# EPS_Connectors_PC-104.net
KiCad netlist of a schematic drawn in Altium Designer
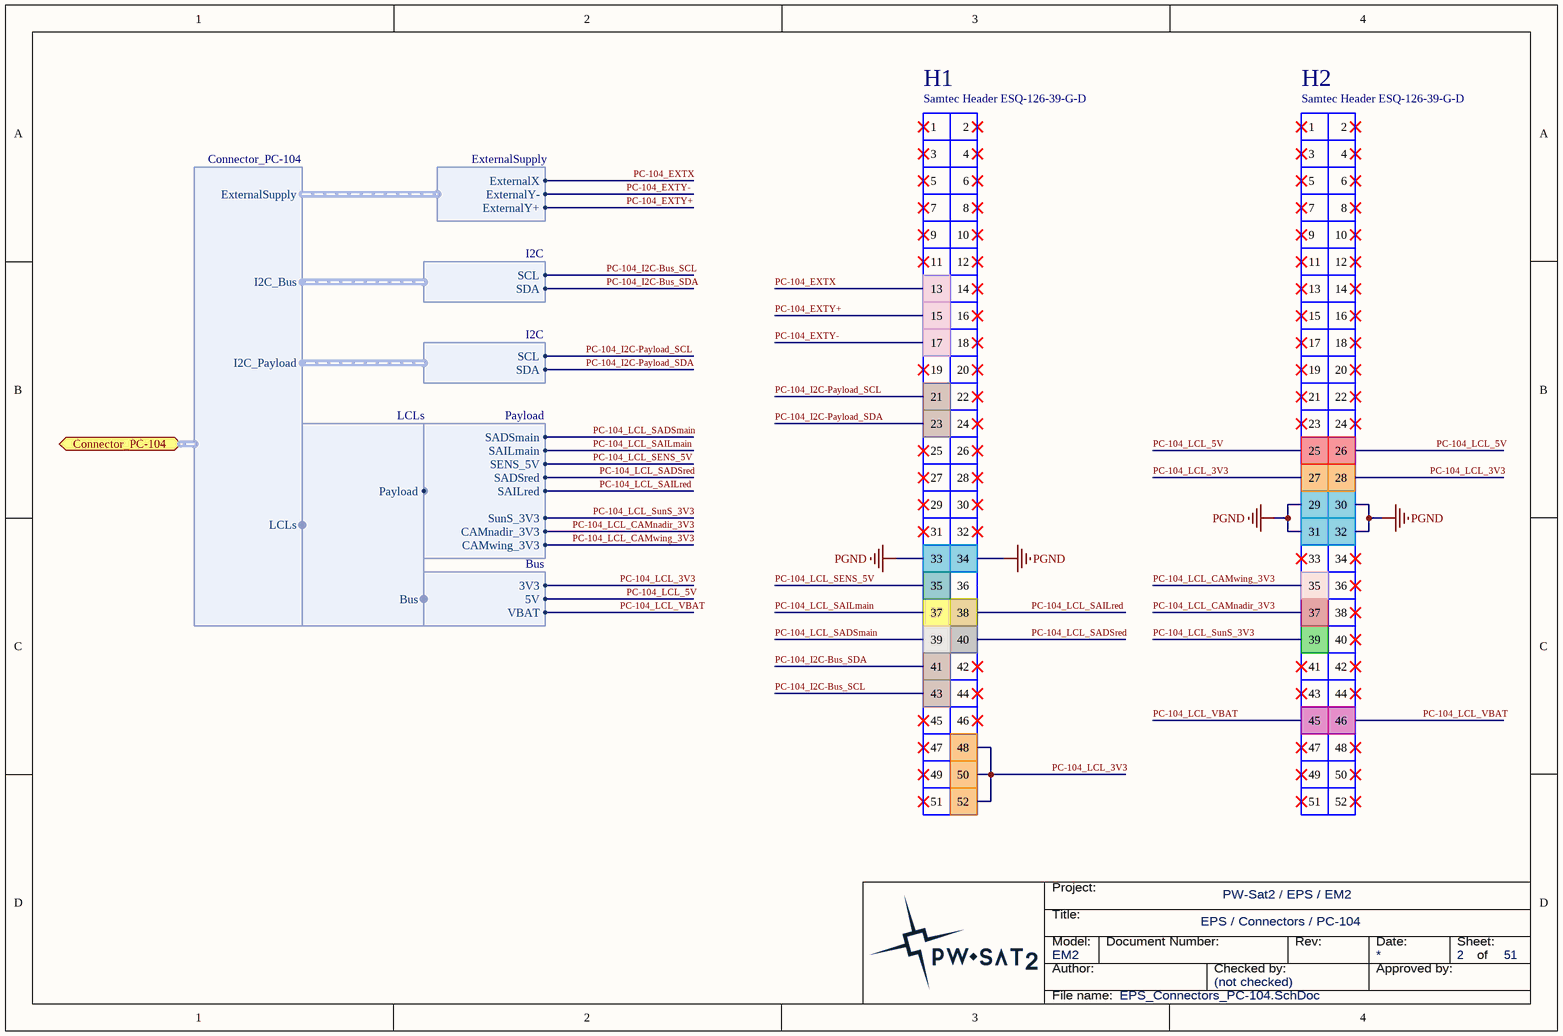
[diagram p0: EPS_Connectors_PC-104.SchDoc]

(export (version "E")
  (design (tool "Eeschema 10.0.6"))
  (components
    (comp (ref "H1")
      (value "Samtec Header ESQ-126-39-G-D")
      (footprint "Samtec_ESQ-126-39-G-D")
      (description "Samtec ESQ Series Header , 2.54mm pitch, 2x26pin. PC-104 Stack Connector.")
      (libsource (lib "connectors_printed-circuit-board") (part "Samtec_ESQ-126-xx-x-D"))
    )
    (comp (ref "H2")
      (value "Samtec Header ESQ-126-39-G-D")
      (footprint "Samtec_ESQ-126-39-G-D")
      (description "Samtec ESQ Series Header , 2.54mm pitch, 2x26pin. PC-104 Stack Connector.")
      (libsource (lib "connectors_printed-circuit-board") (part "Samtec_ESQ-126-xx-x-D"))
    )
  )
  (nets
    (net (code "4") (name "/PC-104_EXTX") (class "Default")
      (node (ref "H1") (pin "13") (pinfunction "13_13") (pintype "passive"))
    )
    (net (code "5") (name "/PC-104_EXTY+") (class "Default")
      (node (ref "H1") (pin "15") (pinfunction "15_15") (pintype "passive"))
    )
    (net (code "6") (name "/PC-104_EXTY-") (class "Default")
      (node (ref "H1") (pin "17") (pinfunction "17_17") (pintype "passive"))
    )
    (net (code "7") (name "/PC-104_I2C-Bus_SCL") (class "Default")
      (node (ref "H1") (pin "43") (pinfunction "43_43") (pintype "passive"))
    )
    (net (code "8") (name "/PC-104_I2C-Bus_SDA") (class "Default")
      (node (ref "H1") (pin "41") (pinfunction "41_41") (pintype "passive"))
    )
    (net (code "9") (name "/PC-104_I2C-Payload_SCL") (class "Default")
      (node (ref "H1") (pin "21") (pinfunction "21_21") (pintype "passive"))
    )
    (net (code "10") (name "/PC-104_I2C-Payload_SDA") (class "Default")
      (node (ref "H1") (pin "23") (pinfunction "23_23") (pintype "passive"))
    )
    (net (code "11") (name "/PC-104_LCL_3V3") (class "Default")
      (node (ref "H1") (pin "48") (pinfunction "48_48") (pintype "passive"))
      (node (ref "H1") (pin "50") (pinfunction "50_50") (pintype "passive"))
      (node (ref "H1") (pin "52") (pinfunction "52_52") (pintype "passive"))
      (node (ref "H2") (pin "27") (pinfunction "27_27") (pintype "passive"))
      (node (ref "H2") (pin "28") (pinfunction "28_28") (pintype "passive"))
    )
    (net (code "12") (name "/PC-104_LCL_5V") (class "Default")
      (node (ref "H2") (pin "25") (pinfunction "25_25") (pintype "passive"))
      (node (ref "H2") (pin "26") (pinfunction "26_26") (pintype "passive"))
    )
    (net (code "13") (name "/PC-104_LCL_CAMnadir_3V3") (class "Default")
      (node (ref "H2") (pin "37") (pinfunction "37_37") (pintype "passive"))
    )
    (net (code "14") (name "/PC-104_LCL_CAMwing_3V3") (class "Default")
      (node (ref "H2") (pin "35") (pinfunction "35_35") (pintype "passive"))
    )
    (net (code "15") (name "/PC-104_LCL_SADSmain") (class "Default")
      (node (ref "H1") (pin "39") (pinfunction "39_39") (pintype "passive"))
    )
    (net (code "16") (name "/PC-104_LCL_SADSred") (class "Default")
      (node (ref "H1") (pin "40") (pinfunction "40_40") (pintype "passive"))
    )
    (net (code "17") (name "/PC-104_LCL_SAILmain") (class "Default")
      (node (ref "H1") (pin "37") (pinfunction "37_37") (pintype "passive"))
    )
    (net (code "18") (name "/PC-104_LCL_SAILred") (class "Default")
      (node (ref "H1") (pin "38") (pinfunction "38_38") (pintype "passive"))
    )
    (net (code "19") (name "/PC-104_LCL_SENS_5V") (class "Default")
      (node (ref "H1") (pin "35") (pinfunction "35_35") (pintype "passive"))
    )
    (net (code "20") (name "/PC-104_LCL_SunS_3V3") (class "Default")
      (node (ref "H2") (pin "39") (pinfunction "39_39") (pintype "passive"))
    )
    (net (code "21") (name "/PC-104_LCL_VBAT") (class "Default")
      (node (ref "H2") (pin "45") (pinfunction "45_45") (pintype "passive"))
      (node (ref "H2") (pin "46") (pinfunction "46_46") (pintype "passive"))
    )
    (net (code "25") (name "PGND") (class "Default")
      (node (ref "H1") (pin "33") (pinfunction "33_33") (pintype "passive"))
      (node (ref "H1") (pin "34") (pinfunction "34_34") (pintype "passive"))
      (node (ref "H2") (pin "29") (pinfunction "29_29") (pintype "passive"))
      (node (ref "H2") (pin "30") (pinfunction "30_30") (pintype "passive"))
      (node (ref "H2") (pin "31") (pinfunction "31_31") (pintype "passive"))
      (node (ref "H2") (pin "32") (pinfunction "32_32") (pintype "passive"))
    )
    (net (code "26") (name "unconnected-(H1-Pad1)") (class "Default")
      (node (ref "H1") (pin "1") (pinfunction "1_1") (pintype "passive+no_connect"))
    )
    (net (code "27") (name "unconnected-(H1-Pad2)") (class "Default")
      (node (ref "H1") (pin "2") (pinfunction "2_2") (pintype "passive+no_connect"))
    )
    (net (code "28") (name "unconnected-(H1-Pad3)") (class "Default")
      (node (ref "H1") (pin "3") (pinfunction "3_3") (pintype "passive+no_connect"))
    )
    (net (code "29") (name "unconnected-(H1-Pad4)") (class "Default")
      (node (ref "H1") (pin "4") (pinfunction "4_4") (pintype "passive+no_connect"))
    )
    (net (code "30") (name "unconnected-(H1-Pad5)") (class "Default")
      (node (ref "H1") (pin "5") (pinfunction "5_5") (pintype "passive+no_connect"))
    )
    (net (code "31") (name "unconnected-(H1-Pad6)") (class "Default")
      (node (ref "H1") (pin "6") (pinfunction "6_6") (pintype "passive+no_connect"))
    )
    (net (code "32") (name "unconnected-(H1-Pad7)") (class "Default")
      (node (ref "H1") (pin "7") (pinfunction "7_7") (pintype "passive+no_connect"))
    )
    (net (code "33") (name "unconnected-(H1-Pad8)") (class "Default")
      (node (ref "H1") (pin "8") (pinfunction "8_8") (pintype "passive+no_connect"))
    )
    (net (code "34") (name "unconnected-(H1-Pad9)") (class "Default")
      (node (ref "H1") (pin "9") (pinfunction "9_9") (pintype "passive+no_connect"))
    )
    (net (code "35") (name "unconnected-(H1-Pad10)") (class "Default")
      (node (ref "H1") (pin "10") (pinfunction "10_10") (pintype "passive+no_connect"))
    )
    (net (code "36") (name "unconnected-(H1-Pad11)") (class "Default")
      (node (ref "H1") (pin "11") (pinfunction "11_11") (pintype "passive+no_connect"))
    )
    (net (code "37") (name "unconnected-(H1-Pad12)") (class "Default")
      (node (ref "H1") (pin "12") (pinfunction "12_12") (pintype "passive+no_connect"))
    )
    (net (code "38") (name "unconnected-(H1-Pad14)") (class "Default")
      (node (ref "H1") (pin "14") (pinfunction "14_14") (pintype "passive+no_connect"))
    )
    (net (code "39") (name "unconnected-(H1-Pad16)") (class "Default")
      (node (ref "H1") (pin "16") (pinfunction "16_16") (pintype "passive+no_connect"))
    )
    (net (code "40") (name "unconnected-(H1-Pad18)") (class "Default")
      (node (ref "H1") (pin "18") (pinfunction "18_18") (pintype "passive+no_connect"))
    )
    (net (code "41") (name "unconnected-(H1-Pad19)") (class "Default")
      (node (ref "H1") (pin "19") (pinfunction "19_19") (pintype "passive+no_connect"))
    )
    (net (code "42") (name "unconnected-(H1-Pad20)") (class "Default")
      (node (ref "H1") (pin "20") (pinfunction "20_20") (pintype "passive+no_connect"))
    )
    (net (code "43") (name "unconnected-(H1-Pad22)") (class "Default")
      (node (ref "H1") (pin "22") (pinfunction "22_22") (pintype "passive+no_connect"))
    )
    (net (code "44") (name "unconnected-(H1-Pad24)") (class "Default")
      (node (ref "H1") (pin "24") (pinfunction "24_24") (pintype "passive+no_connect"))
    )
    (net (code "45") (name "unconnected-(H1-Pad25)") (class "Default")
      (node (ref "H1") (pin "25") (pinfunction "25_25") (pintype "passive+no_connect"))
    )
    (net (code "46") (name "unconnected-(H1-Pad26)") (class "Default")
      (node (ref "H1") (pin "26") (pinfunction "26_26") (pintype "passive+no_connect"))
    )
    (net (code "47") (name "unconnected-(H1-Pad27)") (class "Default")
      (node (ref "H1") (pin "27") (pinfunction "27_27") (pintype "passive+no_connect"))
    )
    (net (code "48") (name "unconnected-(H1-Pad28)") (class "Default")
      (node (ref "H1") (pin "28") (pinfunction "28_28") (pintype "passive+no_connect"))
    )
    (net (code "49") (name "unconnected-(H1-Pad29)") (class "Default")
      (node (ref "H1") (pin "29") (pinfunction "29_29") (pintype "passive+no_connect"))
    )
    (net (code "50") (name "unconnected-(H1-Pad30)") (class "Default")
      (node (ref "H1") (pin "30") (pinfunction "30_30") (pintype "passive+no_connect"))
    )
    (net (code "51") (name "unconnected-(H1-Pad31)") (class "Default")
      (node (ref "H1") (pin "31") (pinfunction "31_31") (pintype "passive+no_connect"))
    )
    (net (code "52") (name "unconnected-(H1-Pad32)") (class "Default")
      (node (ref "H1") (pin "32") (pinfunction "32_32") (pintype "passive+no_connect"))
    )
    (net (code "53") (name "unconnected-(H1-Pad36)") (class "Default")
      (node (ref "H1") (pin "36") (pinfunction "36_36") (pintype "passive"))
    )
    (net (code "54") (name "unconnected-(H1-Pad42)") (class "Default")
      (node (ref "H1") (pin "42") (pinfunction "42_42") (pintype "passive+no_connect"))
    )
    (net (code "55") (name "unconnected-(H1-Pad44)") (class "Default")
      (node (ref "H1") (pin "44") (pinfunction "44_44") (pintype "passive+no_connect"))
    )
    (net (code "56") (name "unconnected-(H1-Pad45)") (class "Default")
      (node (ref "H1") (pin "45") (pinfunction "45_45") (pintype "passive+no_connect"))
    )
    (net (code "57") (name "unconnected-(H1-Pad46)") (class "Default")
      (node (ref "H1") (pin "46") (pinfunction "46_46") (pintype "passive+no_connect"))
    )
    (net (code "58") (name "unconnected-(H1-Pad47)") (class "Default")
      (node (ref "H1") (pin "47") (pinfunction "47_47") (pintype "passive+no_connect"))
    )
    (net (code "59") (name "unconnected-(H1-Pad49)") (class "Default")
      (node (ref "H1") (pin "49") (pinfunction "49_49") (pintype "passive+no_connect"))
    )
    (net (code "60") (name "unconnected-(H1-Pad51)") (class "Default")
      (node (ref "H1") (pin "51") (pinfunction "51_51") (pintype "passive+no_connect"))
    )
    (net (code "61") (name "unconnected-(H2-Pad1)") (class "Default")
      (node (ref "H2") (pin "1") (pinfunction "1_1") (pintype "passive+no_connect"))
    )
    (net (code "62") (name "unconnected-(H2-Pad2)") (class "Default")
      (node (ref "H2") (pin "2") (pinfunction "2_2") (pintype "passive+no_connect"))
    )
    (net (code "63") (name "unconnected-(H2-Pad3)") (class "Default")
      (node (ref "H2") (pin "3") (pinfunction "3_3") (pintype "passive+no_connect"))
    )
    (net (code "64") (name "unconnected-(H2-Pad4)") (class "Default")
      (node (ref "H2") (pin "4") (pinfunction "4_4") (pintype "passive+no_connect"))
    )
    (net (code "65") (name "unconnected-(H2-Pad5)") (class "Default")
      (node (ref "H2") (pin "5") (pinfunction "5_5") (pintype "passive+no_connect"))
    )
    (net (code "66") (name "unconnected-(H2-Pad6)") (class "Default")
      (node (ref "H2") (pin "6") (pinfunction "6_6") (pintype "passive+no_connect"))
    )
    (net (code "67") (name "unconnected-(H2-Pad7)") (class "Default")
      (node (ref "H2") (pin "7") (pinfunction "7_7") (pintype "passive+no_connect"))
    )
    (net (code "68") (name "unconnected-(H2-Pad8)") (class "Default")
      (node (ref "H2") (pin "8") (pinfunction "8_8") (pintype "passive+no_connect"))
    )
    (net (code "69") (name "unconnected-(H2-Pad9)") (class "Default")
      (node (ref "H2") (pin "9") (pinfunction "9_9") (pintype "passive+no_connect"))
    )
    (net (code "70") (name "unconnected-(H2-Pad10)") (class "Default")
      (node (ref "H2") (pin "10") (pinfunction "10_10") (pintype "passive+no_connect"))
    )
    (net (code "71") (name "unconnected-(H2-Pad11)") (class "Default")
      (node (ref "H2") (pin "11") (pinfunction "11_11") (pintype "passive+no_connect"))
    )
    (net (code "72") (name "unconnected-(H2-Pad12)") (class "Default")
      (node (ref "H2") (pin "12") (pinfunction "12_12") (pintype "passive+no_connect"))
    )
    (net (code "73") (name "unconnected-(H2-Pad13)") (class "Default")
      (node (ref "H2") (pin "13") (pinfunction "13_13") (pintype "passive+no_connect"))
    )
    (net (code "74") (name "unconnected-(H2-Pad14)") (class "Default")
      (node (ref "H2") (pin "14") (pinfunction "14_14") (pintype "passive+no_connect"))
    )
    (net (code "75") (name "unconnected-(H2-Pad15)") (class "Default")
      (node (ref "H2") (pin "15") (pinfunction "15_15") (pintype "passive+no_connect"))
    )
    (net (code "76") (name "unconnected-(H2-Pad16)") (class "Default")
      (node (ref "H2") (pin "16") (pinfunction "16_16") (pintype "passive+no_connect"))
    )
    (net (code "77") (name "unconnected-(H2-Pad17)") (class "Default")
      (node (ref "H2") (pin "17") (pinfunction "17_17") (pintype "passive+no_connect"))
    )
    (net (code "78") (name "unconnected-(H2-Pad18)") (class "Default")
      (node (ref "H2") (pin "18") (pinfunction "18_18") (pintype "passive+no_connect"))
    )
    (net (code "79") (name "unconnected-(H2-Pad19)") (class "Default")
      (node (ref "H2") (pin "19") (pinfunction "19_19") (pintype "passive+no_connect"))
    )
    (net (code "80") (name "unconnected-(H2-Pad20)") (class "Default")
      (node (ref "H2") (pin "20") (pinfunction "20_20") (pintype "passive+no_connect"))
    )
    (net (code "81") (name "unconnected-(H2-Pad21)") (class "Default")
      (node (ref "H2") (pin "21") (pinfunction "21_21") (pintype "passive+no_connect"))
    )
    (net (code "82") (name "unconnected-(H2-Pad22)") (class "Default")
      (node (ref "H2") (pin "22") (pinfunction "22_22") (pintype "passive+no_connect"))
    )
    (net (code "83") (name "unconnected-(H2-Pad23)") (class "Default")
      (node (ref "H2") (pin "23") (pinfunction "23_23") (pintype "passive+no_connect"))
    )
    (net (code "84") (name "unconnected-(H2-Pad24)") (class "Default")
      (node (ref "H2") (pin "24") (pinfunction "24_24") (pintype "passive+no_connect"))
    )
    (net (code "85") (name "unconnected-(H2-Pad33)") (class "Default")
      (node (ref "H2") (pin "33") (pinfunction "33_33") (pintype "passive+no_connect"))
    )
    (net (code "86") (name "unconnected-(H2-Pad34)") (class "Default")
      (node (ref "H2") (pin "34") (pinfunction "34_34") (pintype "passive+no_connect"))
    )
    (net (code "87") (name "unconnected-(H2-Pad36)") (class "Default")
      (node (ref "H2") (pin "36") (pinfunction "36_36") (pintype "passive+no_connect"))
    )
    (net (code "88") (name "unconnected-(H2-Pad38)") (class "Default")
      (node (ref "H2") (pin "38") (pinfunction "38_38") (pintype "passive+no_connect"))
    )
    (net (code "89") (name "unconnected-(H2-Pad40)") (class "Default")
      (node (ref "H2") (pin "40") (pinfunction "40_40") (pintype "passive+no_connect"))
    )
    (net (code "90") (name "unconnected-(H2-Pad41)") (class "Default")
      (node (ref "H2") (pin "41") (pinfunction "41_41") (pintype "passive+no_connect"))
    )
    (net (code "91") (name "unconnected-(H2-Pad42)") (class "Default")
      (node (ref "H2") (pin "42") (pinfunction "42_42") (pintype "passive+no_connect"))
    )
    (net (code "92") (name "unconnected-(H2-Pad43)") (class "Default")
      (node (ref "H2") (pin "43") (pinfunction "43_43") (pintype "passive+no_connect"))
    )
    (net (code "93") (name "unconnected-(H2-Pad44)") (class "Default")
      (node (ref "H2") (pin "44") (pinfunction "44_44") (pintype "passive+no_connect"))
    )
    (net (code "94") (name "unconnected-(H2-Pad47)") (class "Default")
      (node (ref "H2") (pin "47") (pinfunction "47_47") (pintype "passive+no_connect"))
    )
    (net (code "95") (name "unconnected-(H2-Pad48)") (class "Default")
      (node (ref "H2") (pin "48") (pinfunction "48_48") (pintype "passive+no_connect"))
    )
    (net (code "96") (name "unconnected-(H2-Pad49)") (class "Default")
      (node (ref "H2") (pin "49") (pinfunction "49_49") (pintype "passive+no_connect"))
    )
    (net (code "97") (name "unconnected-(H2-Pad50)") (class "Default")
      (node (ref "H2") (pin "50") (pinfunction "50_50") (pintype "passive+no_connect"))
    )
    (net (code "98") (name "unconnected-(H2-Pad51)") (class "Default")
      (node (ref "H2") (pin "51") (pinfunction "51_51") (pintype "passive+no_connect"))
    )
    (net (code "99") (name "unconnected-(H2-Pad52)") (class "Default")
      (node (ref "H2") (pin "52") (pinfunction "52_52") (pintype "passive+no_connect"))
    )
  )
)
